# ADC3_2M.net
KiCad netlist of a schematic drawn in EAGLE
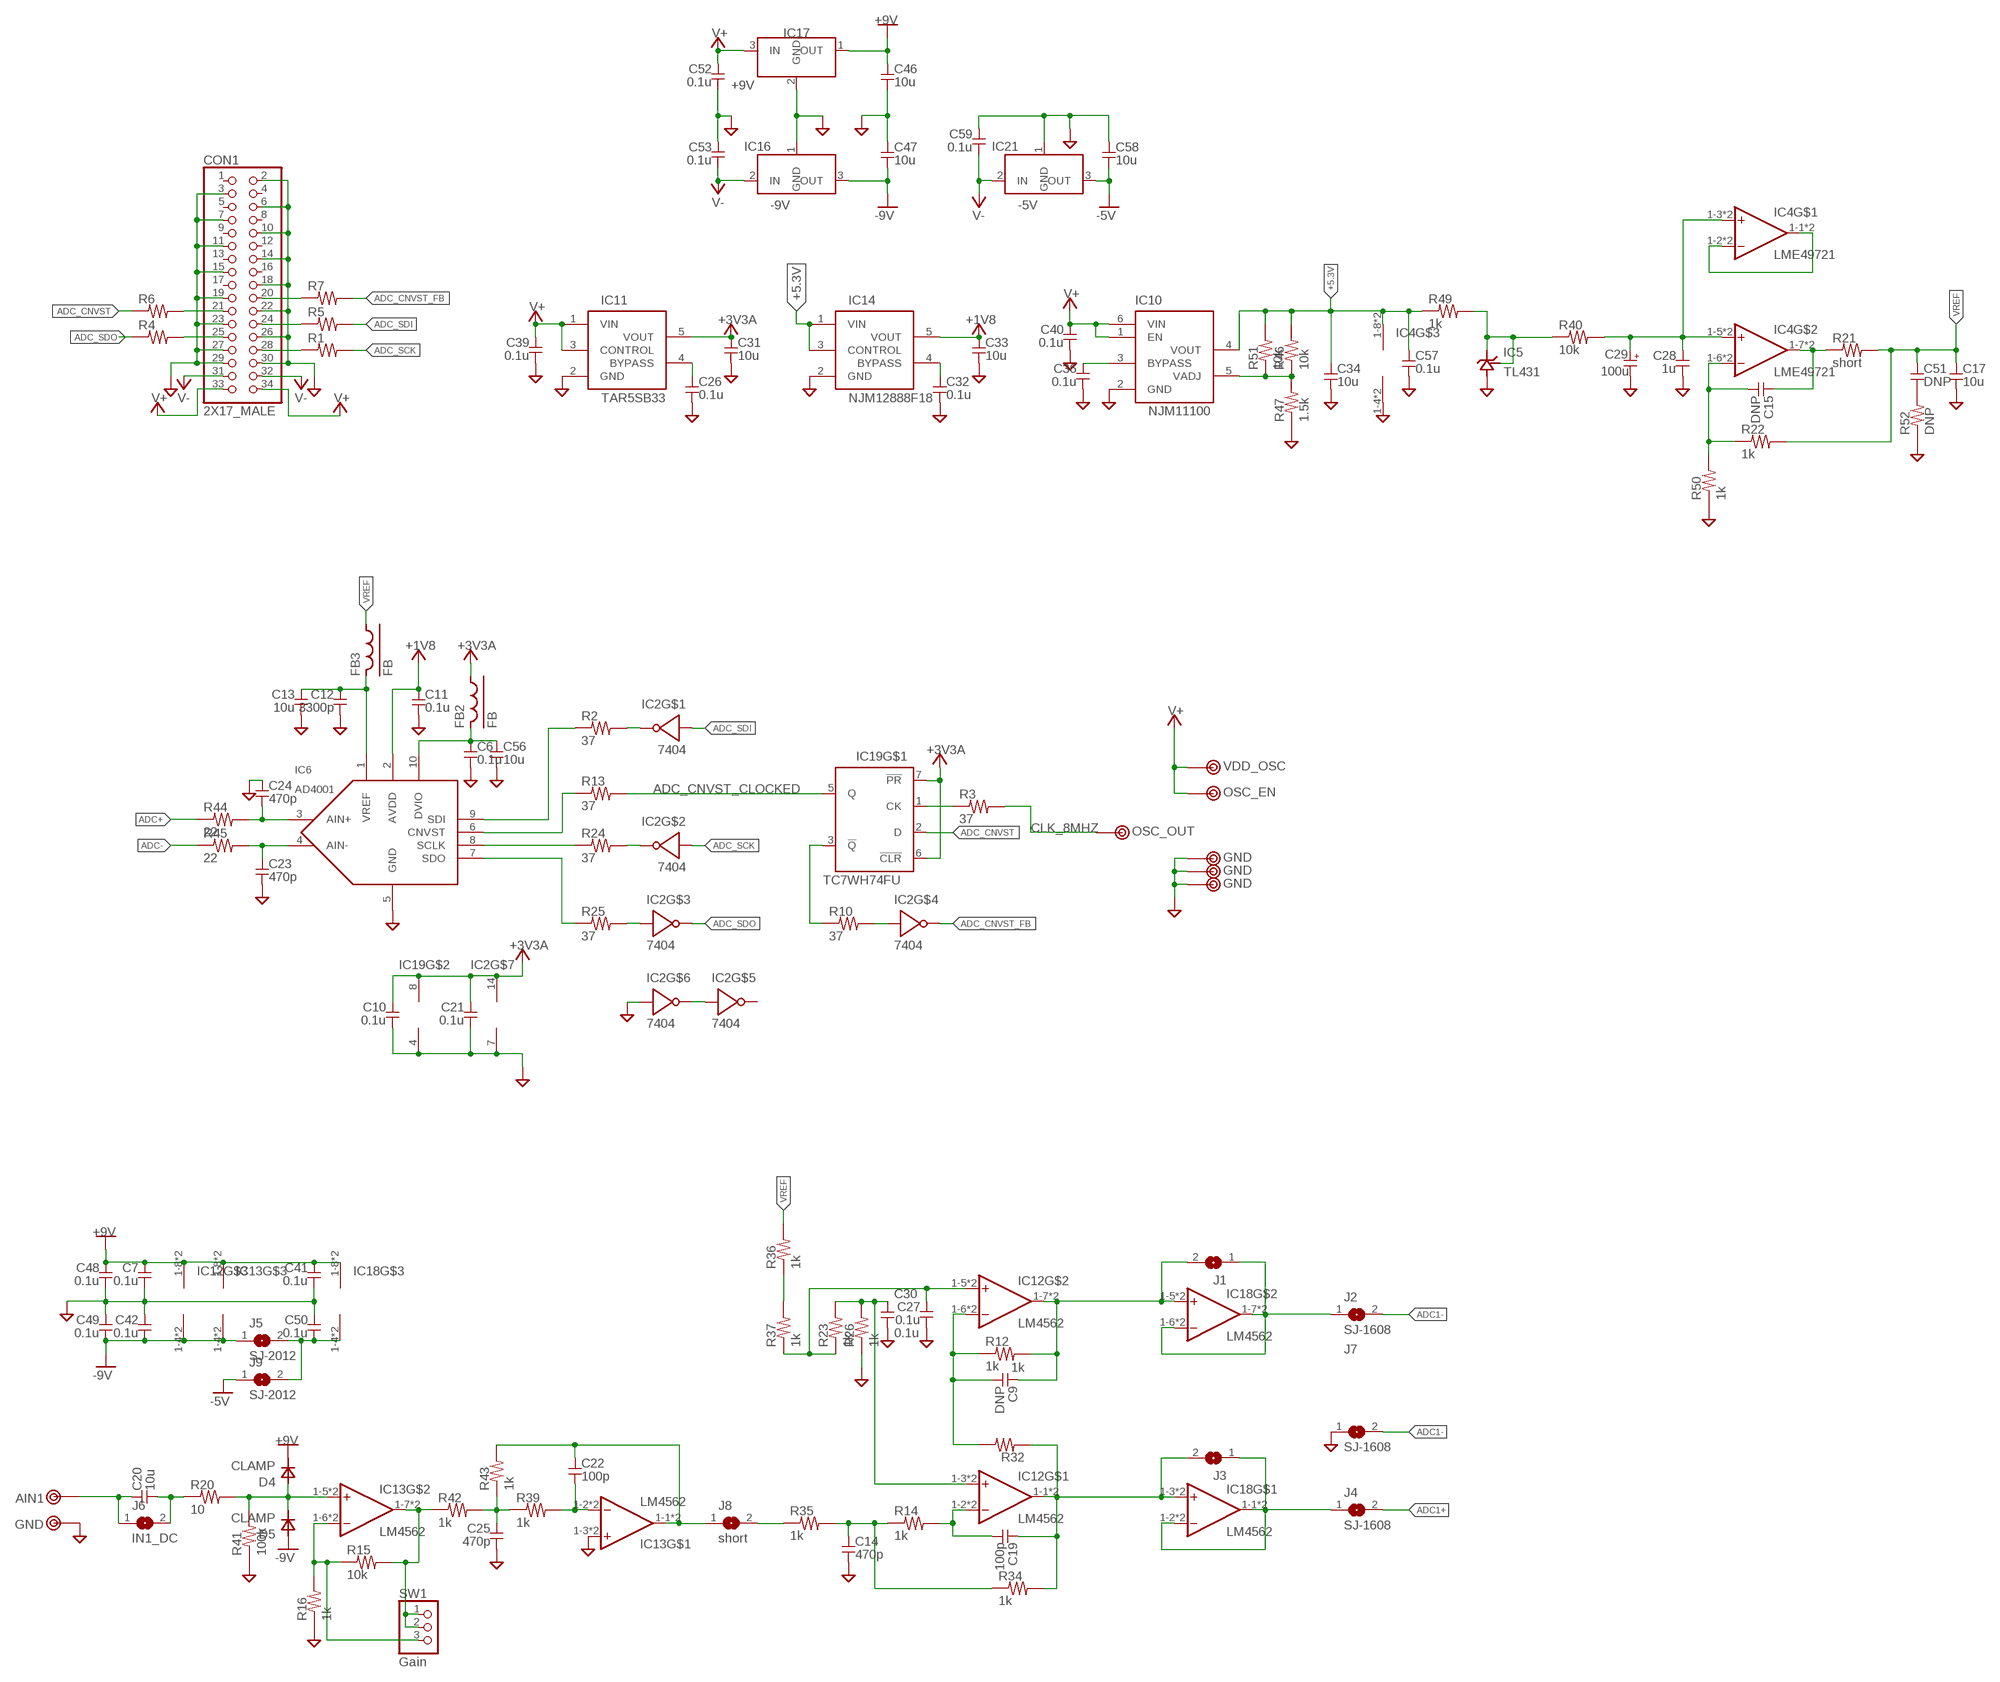
[diagram p0: schematic, sheet 1]

(export (version "E")
  (design (tool "Eeschema 10.0.6"))
  (components
    (comp (ref "C6")
      (value "0.1u")
      (footprint "eagle-import:1608")
      (libsource (lib "eagle-import") (part "C-1608"))
    )
    (comp (ref "C7")
      (value "0.1u")
      (footprint "eagle-import:1608")
      (libsource (lib "eagle-import") (part "C-1608"))
    )
    (comp (ref "C9")
      (value "DNP")
      (footprint "eagle-import:1608")
      (libsource (lib "eagle-import") (part "C-1608"))
    )
    (comp (ref "C10")
      (value "0.1u")
      (footprint "eagle-import:1608")
      (libsource (lib "eagle-import") (part "C-1608"))
    )
    (comp (ref "C11")
      (value "0.1u")
      (footprint "eagle-import:1608")
      (libsource (lib "eagle-import") (part "C-1608"))
    )
    (comp (ref "C12")
      (value "3300p")
      (footprint "eagle-import:1608")
      (libsource (lib "eagle-import") (part "C-1608"))
    )
    (comp (ref "C13")
      (value "10u")
      (footprint "eagle-import:2012")
      (libsource (lib "eagle-import") (part "C-2012"))
    )
    (comp (ref "C14")
      (value "470p")
      (footprint "eagle-import:1608")
      (libsource (lib "eagle-import") (part "C-1608"))
    )
    (comp (ref "C15")
      (value "DNP")
      (footprint "eagle-import:1608")
      (libsource (lib "eagle-import") (part "C-1608"))
    )
    (comp (ref "C17")
      (value "10u")
      (footprint "eagle-import:2012")
      (libsource (lib "eagle-import") (part "C-2012"))
    )
    (comp (ref "C19")
      (value "100p")
      (footprint "eagle-import:1608")
      (libsource (lib "eagle-import") (part "C-1608"))
    )
    (comp (ref "C20")
      (value "10u")
      (footprint "eagle-import:C050")
      (libsource (lib "eagle-import") (part "C-5"))
    )
    (comp (ref "C21")
      (value "0.1u")
      (footprint "eagle-import:1608")
      (libsource (lib "eagle-import") (part "C-1608"))
    )
    (comp (ref "C22")
      (value "100p")
      (footprint "eagle-import:1608")
      (libsource (lib "eagle-import") (part "C-1608"))
    )
    (comp (ref "C23")
      (value "470p")
      (footprint "eagle-import:1608")
      (libsource (lib "eagle-import") (part "C-1608"))
    )
    (comp (ref "C24")
      (value "470p")
      (footprint "eagle-import:1608")
      (libsource (lib "eagle-import") (part "C-1608"))
    )
    (comp (ref "C25")
      (value "470p")
      (footprint "eagle-import:1608")
      (libsource (lib "eagle-import") (part "C-1608"))
    )
    (comp (ref "C26")
      (value "0.1u")
      (footprint "eagle-import:1608")
      (libsource (lib "eagle-import") (part "C-1608"))
    )
    (comp (ref "C27")
      (value "0.1u")
      (footprint "eagle-import:1608")
      (libsource (lib "eagle-import") (part "C-1608"))
    )
    (comp (ref "C28")
      (value "1u")
      (footprint "eagle-import:1608")
      (libsource (lib "eagle-import") (part "C-1608"))
    )
    (comp (ref "C29")
      (value "100u")
      (footprint "eagle-import:E2.5-6.5")
      (libsource (lib "eagle-import") (part "CPOLE2.5-6.5"))
    )
    (comp (ref "C30")
      (value "0.1u")
      (footprint "eagle-import:1608")
      (libsource (lib "eagle-import") (part "C-1608"))
    )
    (comp (ref "C31")
      (value "10u")
      (footprint "eagle-import:2012")
      (libsource (lib "eagle-import") (part "C-2012"))
    )
    (comp (ref "C32")
      (value "0.1u")
      (footprint "eagle-import:1608")
      (libsource (lib "eagle-import") (part "C-1608"))
    )
    (comp (ref "C33")
      (value "10u")
      (footprint "eagle-import:2012")
      (libsource (lib "eagle-import") (part "C-2012"))
    )
    (comp (ref "C34")
      (value "10u")
      (footprint "eagle-import:2012")
      (libsource (lib "eagle-import") (part "C-2012"))
    )
    (comp (ref "C36")
      (value "0.1u")
      (footprint "eagle-import:1608")
      (libsource (lib "eagle-import") (part "C-1608"))
    )
    (comp (ref "C39")
      (value "0.1u")
      (footprint "eagle-import:1608")
      (libsource (lib "eagle-import") (part "C-1608"))
    )
    (comp (ref "C40")
      (value "0.1u")
      (footprint "eagle-import:1608")
      (libsource (lib "eagle-import") (part "C-1608"))
    )
    (comp (ref "C41")
      (value "0.1u")
      (footprint "eagle-import:1608")
      (libsource (lib "eagle-import") (part "C-1608"))
    )
    (comp (ref "C42")
      (value "0.1u")
      (footprint "eagle-import:1608")
      (libsource (lib "eagle-import") (part "C-1608"))
    )
    (comp (ref "C46")
      (value "10u")
      (footprint "eagle-import:3216")
      (libsource (lib "eagle-import") (part "C-3216"))
    )
    (comp (ref "C47")
      (value "10u")
      (footprint "eagle-import:3216")
      (libsource (lib "eagle-import") (part "C-3216"))
    )
    (comp (ref "C48")
      (value "0.1u")
      (footprint "eagle-import:1608")
      (libsource (lib "eagle-import") (part "C-1608"))
    )
    (comp (ref "C49")
      (value "0.1u")
      (footprint "eagle-import:1608")
      (libsource (lib "eagle-import") (part "C-1608"))
    )
    (comp (ref "C50")
      (value "0.1u")
      (footprint "eagle-import:1608")
      (libsource (lib "eagle-import") (part "C-1608"))
    )
    (comp (ref "C51")
      (value "DNP")
      (footprint "eagle-import:2012")
      (libsource (lib "eagle-import") (part "C-2012"))
    )
    (comp (ref "C52")
      (value "0.1u")
      (footprint "eagle-import:1608")
      (libsource (lib "eagle-import") (part "C-1608"))
    )
    (comp (ref "C53")
      (value "0.1u")
      (footprint "eagle-import:1608")
      (libsource (lib "eagle-import") (part "C-1608"))
    )
    (comp (ref "C56")
      (value "10u")
      (footprint "eagle-import:2012")
      (libsource (lib "eagle-import") (part "C-2012"))
    )
    (comp (ref "C57")
      (value "0.1u")
      (footprint "eagle-import:1608")
      (libsource (lib "eagle-import") (part "C-1608"))
    )
    (comp (ref "C58")
      (value "10u")
      (footprint "eagle-import:2012")
      (libsource (lib "eagle-import") (part "C-2012"))
    )
    (comp (ref "C59")
      (value "0.1u")
      (footprint "eagle-import:1608")
      (libsource (lib "eagle-import") (part "C-1608"))
    )
    (comp (ref "CON1")
      (value "2X17_MALE")
      (footprint "eagle-import:2X17_90")
      (libsource (lib "eagle-import") (part "2X17_MALE"))
    )
    (comp (ref "D4")
      (value "CLAMP")
      (footprint "eagle-import:SOD123")
      (libsource (lib "eagle-import") (part "DIODE-1N4148W"))
    )
    (comp (ref "D5")
      (value "CLAMP")
      (footprint "eagle-import:SOD123")
      (libsource (lib "eagle-import") (part "DIODE-1N4148W"))
    )
    (comp (ref "FB2")
      (value "FB")
      (footprint "eagle-import:1608-J")
      (libsource (lib "eagle-import") (part "FB"))
    )
    (comp (ref "FB3")
      (value "FB")
      (footprint "eagle-import:1608-J")
      (libsource (lib "eagle-import") (part "FB"))
    )
    (comp (ref "IC2")
      (value "7404")
      (footprint "eagle-import:TSSOP14")
      (libsource (lib "eagle-import") (part "7404"))
    )
    (comp (ref "IC4")
      (value "LME49721")
      (footprint "eagle-import:DIL8-SOP8")
      (libsource (lib "eagle-import") (part "OPA-2-DUAL"))
    )
    (comp (ref "IC5")
      (value "TL431")
      (footprint "eagle-import:TO-92")
      (libsource (lib "eagle-import") (part "TL431"))
    )
    (comp (ref "IC6")
      (value "AD4001")
      (footprint "eagle-import:MSOP10")
      (libsource (lib "eagle-import") (part "MCP331X1"))
    )
    (comp (ref "IC10")
      (value "NJM11100")
      (footprint "eagle-import:SOT23-6")
      (libsource (lib "eagle-import") (part "NJM11100"))
    )
    (comp (ref "IC11")
      (value "TAR5SB33")
      (footprint "eagle-import:SOT23-5")
      (libsource (lib "eagle-import") (part "TAR5SB33"))
    )
    (comp (ref "IC12")
      (value "LM4562")
      (footprint "eagle-import:DIL8-SOP8")
      (libsource (lib "eagle-import") (part "OPA-2-DUAL"))
    )
    (comp (ref "IC13")
      (value "LM4562")
      (footprint "eagle-import:DIL8-SOP8")
      (libsource (lib "eagle-import") (part "OPA-2-DUAL"))
    )
    (comp (ref "IC14")
      (value "NJM12888F18")
      (footprint "eagle-import:SOT23-5")
      (libsource (lib "eagle-import") (part "NJM12888"))
    )
    (comp (ref "IC16")
      (value "-9V")
      (footprint "eagle-import:TO-92")
      (libsource (lib "eagle-import") (part "79LX"))
    )
    (comp (ref "IC17")
      (value "+9V")
      (footprint "eagle-import:TO-92")
      (libsource (lib "eagle-import") (part "78LX"))
    )
    (comp (ref "IC18")
      (value "LM4562")
      (footprint "eagle-import:DIL8-SOP8")
      (libsource (lib "eagle-import") (part "OPA-2-DUAL"))
    )
    (comp (ref "IC19")
      (value "TC7WH74FU")
      (footprint "eagle-import:SSOP8-P-0.65")
      (libsource (lib "eagle-import") (part "TC7WH74FU"))
    )
    (comp (ref "IC21")
      (value "-5V")
      (footprint "eagle-import:TO-92")
      (libsource (lib "eagle-import") (part "79LX"))
    )
    (comp (ref "J1")
      (value "SJ-2012")
      (footprint "eagle-import:2012-J")
      (libsource (lib "eagle-import") (part "SJ-2012"))
    )
    (comp (ref "J2")
      (value "SJ-1608")
      (footprint "eagle-import:1608-J")
      (libsource (lib "eagle-import") (part "SJ-1608"))
    )
    (comp (ref "J3")
      (value "SJ-2012")
      (footprint "eagle-import:2012-J")
      (libsource (lib "eagle-import") (part "SJ-2012"))
    )
    (comp (ref "J4")
      (value "SJ-1608")
      (footprint "eagle-import:1608-J")
      (libsource (lib "eagle-import") (part "SJ-1608"))
    )
    (comp (ref "J5")
      (value "SJ-2012")
      (footprint "eagle-import:2012-J")
      (libsource (lib "eagle-import") (part "SJ-2012"))
    )
    (comp (ref "J6")
      (value "IN1_DC")
      (footprint "eagle-import:2012-J")
      (libsource (lib "eagle-import") (part "SJ-2012"))
    )
    (comp (ref "J7")
      (value "SJ-1608")
      (footprint "eagle-import:1608-J")
      (libsource (lib "eagle-import") (part "SJ-1608"))
    )
    (comp (ref "J8")
      (value "short")
      (footprint "eagle-import:2012-J")
      (libsource (lib "eagle-import") (part "SJ-2012"))
    )
    (comp (ref "J9")
      (value "SJ-2012")
      (footprint "eagle-import:2012-J")
      (libsource (lib "eagle-import") (part "SJ-2012"))
    )
    (comp (ref "R1")
      (value "R-1608J")
      (footprint "eagle-import:1608-J")
      (libsource (lib "eagle-import") (part "R-1608J"))
    )
    (comp (ref "R2")
      (value "37")
      (footprint "eagle-import:1608-J")
      (libsource (lib "eagle-import") (part "R-1608J"))
    )
    (comp (ref "R3")
      (value "37")
      (footprint "eagle-import:1608-J")
      (libsource (lib "eagle-import") (part "R-1608J"))
    )
    (comp (ref "R4")
      (value "R-1608J")
      (footprint "eagle-import:1608-J")
      (libsource (lib "eagle-import") (part "R-1608J"))
    )
    (comp (ref "R5")
      (value "R-1608J")
      (footprint "eagle-import:1608-J")
      (libsource (lib "eagle-import") (part "R-1608J"))
    )
    (comp (ref "R6")
      (value "R-1608J")
      (footprint "eagle-import:1608-J")
      (libsource (lib "eagle-import") (part "R-1608J"))
    )
    (comp (ref "R7")
      (value "R-1608J")
      (footprint "eagle-import:1608-J")
      (libsource (lib "eagle-import") (part "R-1608J"))
    )
    (comp (ref "R10")
      (value "37")
      (footprint "eagle-import:1608-J")
      (libsource (lib "eagle-import") (part "R-1608J"))
    )
    (comp (ref "R12")
      (value "1k")
      (footprint "eagle-import:1608")
      (libsource (lib "eagle-import") (part "R-1608"))
    )
    (comp (ref "R13")
      (value "37")
      (footprint "eagle-import:1608-J")
      (libsource (lib "eagle-import") (part "R-1608J"))
    )
    (comp (ref "R14")
      (value "1k")
      (footprint "eagle-import:1608")
      (libsource (lib "eagle-import") (part "R-1608"))
    )
    (comp (ref "R15")
      (value "10k")
      (footprint "eagle-import:1608")
      (libsource (lib "eagle-import") (part "R-1608"))
    )
    (comp (ref "R16")
      (value "1k")
      (footprint "eagle-import:1608")
      (libsource (lib "eagle-import") (part "R-1608"))
    )
    (comp (ref "R20")
      (value "10")
      (footprint "eagle-import:1608-J")
      (libsource (lib "eagle-import") (part "R-1608J"))
    )
    (comp (ref "R21")
      (value "short")
      (footprint "eagle-import:1608-J")
      (libsource (lib "eagle-import") (part "R-1608J"))
    )
    (comp (ref "R22")
      (value "1k")
      (footprint "eagle-import:1608")
      (libsource (lib "eagle-import") (part "R-1608"))
    )
    (comp (ref "R23")
      (value "1k")
      (footprint "eagle-import:1608")
      (libsource (lib "eagle-import") (part "R-1608"))
    )
    (comp (ref "R24")
      (value "37")
      (footprint "eagle-import:1608-J")
      (libsource (lib "eagle-import") (part "R-1608J"))
    )
    (comp (ref "R25")
      (value "37")
      (footprint "eagle-import:1608-J")
      (libsource (lib "eagle-import") (part "R-1608J"))
    )
    (comp (ref "R26")
      (value "1k")
      (footprint "eagle-import:1608")
      (libsource (lib "eagle-import") (part "R-1608"))
    )
    (comp (ref "R32")
      (value "1k")
      (footprint "eagle-import:1608")
      (libsource (lib "eagle-import") (part "R-1608"))
    )
    (comp (ref "R34")
      (value "1k")
      (footprint "eagle-import:1608")
      (libsource (lib "eagle-import") (part "R-1608"))
    )
    (comp (ref "R35")
      (value "1k")
      (footprint "eagle-import:1608")
      (libsource (lib "eagle-import") (part "R-1608"))
    )
    (comp (ref "R36")
      (value "1k")
      (footprint "eagle-import:1608")
      (libsource (lib "eagle-import") (part "R-1608"))
    )
    (comp (ref "R37")
      (value "1k")
      (footprint "eagle-import:1608")
      (libsource (lib "eagle-import") (part "R-1608"))
    )
    (comp (ref "R39")
      (value "1k")
      (footprint "eagle-import:1608")
      (libsource (lib "eagle-import") (part "R-1608"))
    )
    (comp (ref "R40")
      (value "10k")
      (footprint "eagle-import:1608")
      (libsource (lib "eagle-import") (part "R-1608"))
    )
    (comp (ref "R41")
      (value "100k")
      (footprint "eagle-import:1608")
      (libsource (lib "eagle-import") (part "R-1608"))
    )
    (comp (ref "R42")
      (value "1k")
      (footprint "eagle-import:1608")
      (libsource (lib "eagle-import") (part "R-1608"))
    )
    (comp (ref "R43")
      (value "1k")
      (footprint "eagle-import:1608")
      (libsource (lib "eagle-import") (part "R-1608"))
    )
    (comp (ref "R44")
      (value "22")
      (footprint "eagle-import:1608")
      (libsource (lib "eagle-import") (part "R-1608"))
    )
    (comp (ref "R45")
      (value "22")
      (footprint "eagle-import:1608")
      (libsource (lib "eagle-import") (part "R-1608"))
    )
    (comp (ref "R46")
      (value "10k")
      (footprint "eagle-import:1608")
      (libsource (lib "eagle-import") (part "R-1608"))
    )
    (comp (ref "R47")
      (value "1.5k")
      (footprint "eagle-import:1608")
      (libsource (lib "eagle-import") (part "R-1608"))
    )
    (comp (ref "R49")
      (value "1k")
      (footprint "eagle-import:1608")
      (libsource (lib "eagle-import") (part "R-1608"))
    )
    (comp (ref "R50")
      (value "1k")
      (footprint "eagle-import:1608")
      (libsource (lib "eagle-import") (part "R-1608"))
    )
    (comp (ref "R51")
      (value "10k")
      (footprint "eagle-import:1608")
      (libsource (lib "eagle-import") (part "R-1608"))
    )
    (comp (ref "R52")
      (value "DNP")
      (footprint "eagle-import:2012")
      (libsource (lib "eagle-import") (part "R-2012"))
    )
    (comp (ref "SW1")
      (value "Gain")
      (footprint "eagle-import:1X03")
      (libsource (lib "eagle-import") (part "SW-1X3"))
    )
    (comp (ref "TP2")
      (value "AIN1")
      (footprint "eagle-import:TESTPIN-BIG")
      (libsource (lib "eagle-import") (part "TESTPIN-BIG"))
    )
    (comp (ref "TP16")
      (value "GND")
      (footprint "eagle-import:TESTPIN-BIG")
      (libsource (lib "eagle-import") (part "TESTPIN-BIG"))
    )
    (comp (ref "TP24")
      (value "VDD_OSC")
      (footprint "eagle-import:TESTPIN")
      (libsource (lib "eagle-import") (part "TESTPIN"))
    )
    (comp (ref "TP25")
      (value "OSC_EN")
      (footprint "eagle-import:TESTPIN")
      (libsource (lib "eagle-import") (part "TESTPIN"))
    )
    (comp (ref "TP26")
      (value "OSC_OUT")
      (footprint "eagle-import:TESTPIN")
      (libsource (lib "eagle-import") (part "TESTPIN"))
    )
    (comp (ref "TP27")
      (value "GND")
      (footprint "eagle-import:TESTPIN")
      (libsource (lib "eagle-import") (part "TESTPIN"))
    )
    (comp (ref "TP28")
      (value "GND")
      (footprint "eagle-import:TESTPIN")
      (libsource (lib "eagle-import") (part "TESTPIN"))
    )
    (comp (ref "TP29")
      (value "GND")
      (footprint "eagle-import:TESTPIN")
      (libsource (lib "eagle-import") (part "TESTPIN"))
    )
  )
  (nets
    (net (code "1") (name "+1V8") (class "Default")
      (node (ref "C11") (pin "1") (pinfunction "1_1") (pintype "passive"))
      (node (ref "C33") (pin "1") (pinfunction "1_1") (pintype "passive"))
      (node (ref "IC14") (pin "5") (pinfunction "VOUT_5") (pintype "power_in"))
      (node (ref "IC6") (pin "2") (pinfunction "AVDD_2") (pintype "power_in"))
    )
    (net (code "2") (name "+3V3A") (class "Default")
      (node (ref "C10") (pin "1") (pinfunction "1_1") (pintype "passive"))
      (node (ref "C21") (pin "1") (pinfunction "1_1") (pintype "passive"))
      (node (ref "C31") (pin "1") (pinfunction "1_1") (pintype "passive"))
      (node (ref "FB2") (pin "1") (pinfunction "1_1") (pintype "passive"))
      (node (ref "IC11") (pin "5") (pinfunction "VOUT_5") (pintype "power_in"))
      (node (ref "IC19") (pin "6") (pinfunction "~{CLR}_6") (pintype "input"))
      (node (ref "IC19") (pin "7") (pinfunction "~{PR}_7") (pintype "input"))
      (node (ref "IC19") (pin "8") (pinfunction "V+_8") (pintype "power_in"))
      (node (ref "IC2") (pin "14") (pinfunction "V+_14") (pintype "power_in"))
    )
    (net (code "3") (name "+5.3V") (class "Default")
      (node (ref "C34") (pin "1") (pinfunction "1_1") (pintype "passive"))
      (node (ref "C57") (pin "1") (pinfunction "1_1") (pintype "passive"))
      (node (ref "IC10") (pin "4") (pinfunction "VOUT_4") (pintype "output"))
      (node (ref "IC14") (pin "1") (pinfunction "VIN_1") (pintype "power_in"))
      (node (ref "IC14") (pin "3") (pinfunction "CONTROL_3") (pintype "input"))
      (node (ref "IC4") (pin "1-8") (pinfunction "V+_1-8") (pintype "power_in"))
      (node (ref "IC4") (pin "2-8") (pinfunction "V+_2-8") (pintype "power_in"))
      (node (ref "R46") (pin "2") (pinfunction "2_2") (pintype "passive"))
      (node (ref "R49") (pin "1") (pinfunction "1_1") (pintype "passive"))
      (node (ref "R51") (pin "2") (pinfunction "2_2") (pintype "passive"))
    )
    (net (code "4") (name "+9V") (class "Default")
      (node (ref "C41") (pin "1") (pinfunction "1_1") (pintype "passive"))
      (node (ref "C46") (pin "1") (pinfunction "1_1") (pintype "passive"))
      (node (ref "C48") (pin "1") (pinfunction "1_1") (pintype "passive"))
      (node (ref "C7") (pin "1") (pinfunction "1_1") (pintype "passive"))
      (node (ref "D4") (pin "2") (pinfunction "K_2") (pintype "passive"))
      (node (ref "IC12") (pin "1-8") (pinfunction "V+_1-8") (pintype "power_in"))
      (node (ref "IC12") (pin "2-8") (pinfunction "V+_2-8") (pintype "power_in"))
      (node (ref "IC13") (pin "1-8") (pinfunction "V+_1-8") (pintype "power_in"))
      (node (ref "IC13") (pin "2-8") (pinfunction "V+_2-8") (pintype "power_in"))
      (node (ref "IC17") (pin "1") (pinfunction "OUT_1") (pintype "output"))
      (node (ref "IC18") (pin "1-8") (pinfunction "V+_1-8") (pintype "power_in"))
      (node (ref "IC18") (pin "2-8") (pinfunction "V+_2-8") (pintype "power_in"))
    )
    (net (code "5") (name "-5V") (class "Default")
      (node (ref "C58") (pin "2") (pinfunction "2_2") (pintype "passive"))
      (node (ref "IC21") (pin "3") (pinfunction "OUT_3") (pintype "output"))
      (node (ref "J9") (pin "1") (pinfunction "1_1") (pintype "passive"))
    )
    (net (code "6") (name "-9V") (class "Default")
      (node (ref "C42") (pin "2") (pinfunction "2_2") (pintype "passive"))
      (node (ref "C47") (pin "2") (pinfunction "2_2") (pintype "passive"))
      (node (ref "C49") (pin "2") (pinfunction "2_2") (pintype "passive"))
      (node (ref "D5") (pin "1") (pinfunction "A_1") (pintype "passive"))
      (node (ref "IC12") (pin "1-4") (pinfunction "V-_1-4") (pintype "power_in"))
      (node (ref "IC12") (pin "2-4") (pinfunction "V-_2-4") (pintype "power_in"))
      (node (ref "IC13") (pin "1-4") (pinfunction "V-_1-4") (pintype "power_in"))
      (node (ref "IC13") (pin "2-4") (pinfunction "V-_2-4") (pintype "power_in"))
      (node (ref "IC16") (pin "3") (pinfunction "OUT_3") (pintype "output"))
      (node (ref "J5") (pin "1") (pinfunction "1_1") (pintype "passive"))
    )
    (net (code "7") (name "/ADC_CNVST_CLOCKED") (class "Default")
      (node (ref "IC19") (pin "5") (pinfunction "Q_5") (pintype "output"))
      (node (ref "R13") (pin "2") (pinfunction "2_2") (pintype "passive"))
    )
    (net (code "8") (name "/CLK_8MHZ") (class "Default")
      (node (ref "R3") (pin "2") (pinfunction "2_2") (pintype "passive"))
      (node (ref "TP26") (pin "1") (pinfunction "1_1") (pintype "passive"))
    )
    (net (code "9") (name "ADC+") (class "Default")
      (node (ref "R44") (pin "1") (pinfunction "1_1") (pintype "passive"))
    )
    (net (code "10") (name "ADC-") (class "Default")
      (node (ref "R45") (pin "1") (pinfunction "1_1") (pintype "passive"))
    )
    (net (code "11") (name "ADC1+") (class "Default")
      (node (ref "J4") (pin "2") (pinfunction "2_2") (pintype "passive"))
    )
    (net (code "12") (name "ADC1-") (class "Default")
      (node (ref "J2") (pin "2") (pinfunction "2_2") (pintype "passive"))
      (node (ref "J7") (pin "2") (pinfunction "2_2") (pintype "passive"))
    )
    (net (code "13") (name "ADC_CNVST") (class "Default")
      (node (ref "IC19") (pin "2") (pinfunction "D_2") (pintype "input"))
      (node (ref "R6") (pin "1") (pinfunction "1_1") (pintype "passive"))
    )
    (net (code "14") (name "ADC_CNVST_FB") (class "Default")
      (node (ref "IC2") (pin "8") (pinfunction "OUT_8") (pintype "output"))
      (node (ref "R7") (pin "2") (pinfunction "2_2") (pintype "passive"))
    )
    (net (code "15") (name "ADC_SCK") (class "Default")
      (node (ref "IC2") (pin "3") (pinfunction "IN_3") (pintype "input"))
      (node (ref "R1") (pin "2") (pinfunction "2_2") (pintype "passive"))
    )
    (net (code "16") (name "ADC_SDI") (class "Default")
      (node (ref "IC2") (pin "1") (pinfunction "IN_1") (pintype "input"))
      (node (ref "R5") (pin "2") (pinfunction "2_2") (pintype "passive"))
    )
    (net (code "17") (name "ADC_SDO") (class "Default")
      (node (ref "IC2") (pin "6") (pinfunction "OUT_6") (pintype "output"))
      (node (ref "R4") (pin "1") (pinfunction "1_1") (pintype "passive"))
    )
    (net (code "18") (name "GND") (class "Default")
      (node (ref "C10") (pin "2") (pinfunction "2_2") (pintype "passive"))
      (node (ref "C11") (pin "2") (pinfunction "2_2") (pintype "passive"))
      (node (ref "C12") (pin "2") (pinfunction "2_2") (pintype "passive"))
      (node (ref "C13") (pin "2") (pinfunction "2_2") (pintype "passive"))
      (node (ref "C14") (pin "2") (pinfunction "2_2") (pintype "passive"))
      (node (ref "C17") (pin "2") (pinfunction "2_2") (pintype "passive"))
      (node (ref "C21") (pin "2") (pinfunction "2_2") (pintype "passive"))
      (node (ref "C23") (pin "2") (pinfunction "2_2") (pintype "passive"))
      (node (ref "C24") (pin "1") (pinfunction "1_1") (pintype "passive"))
      (node (ref "C25") (pin "2") (pinfunction "2_2") (pintype "passive"))
      (node (ref "C26") (pin "2") (pinfunction "2_2") (pintype "passive"))
      (node (ref "C27") (pin "2") (pinfunction "2_2") (pintype "passive"))
      (node (ref "C28") (pin "2") (pinfunction "2_2") (pintype "passive"))
      (node (ref "C29") (pin "-") (pinfunction "2_-") (pintype "passive"))
      (node (ref "C30") (pin "2") (pinfunction "2_2") (pintype "passive"))
      (node (ref "C31") (pin "2") (pinfunction "2_2") (pintype "passive"))
      (node (ref "C32") (pin "2") (pinfunction "2_2") (pintype "passive"))
      (node (ref "C33") (pin "2") (pinfunction "2_2") (pintype "passive"))
      (node (ref "C34") (pin "2") (pinfunction "2_2") (pintype "passive"))
      (node (ref "C36") (pin "2") (pinfunction "2_2") (pintype "passive"))
      (node (ref "C39") (pin "2") (pinfunction "2_2") (pintype "passive"))
      (node (ref "C40") (pin "2") (pinfunction "2_2") (pintype "passive"))
      (node (ref "C41") (pin "2") (pinfunction "2_2") (pintype "passive"))
      (node (ref "C42") (pin "1") (pinfunction "1_1") (pintype "passive"))
      (node (ref "C46") (pin "2") (pinfunction "2_2") (pintype "passive"))
      (node (ref "C47") (pin "1") (pinfunction "1_1") (pintype "passive"))
      (node (ref "C48") (pin "2") (pinfunction "2_2") (pintype "passive"))
      (node (ref "C49") (pin "1") (pinfunction "1_1") (pintype "passive"))
      (node (ref "C50") (pin "1") (pinfunction "1_1") (pintype "passive"))
      (node (ref "C52") (pin "2") (pinfunction "2_2") (pintype "passive"))
      (node (ref "C53") (pin "1") (pinfunction "1_1") (pintype "passive"))
      (node (ref "C56") (pin "2") (pinfunction "2_2") (pintype "passive"))
      (node (ref "C57") (pin "2") (pinfunction "2_2") (pintype "passive"))
      (node (ref "C58") (pin "1") (pinfunction "1_1") (pintype "passive"))
      (node (ref "C59") (pin "1") (pinfunction "1_1") (pintype "passive"))
      (node (ref "C6") (pin "2") (pinfunction "2_2") (pintype "passive"))
      (node (ref "C7") (pin "2") (pinfunction "2_2") (pintype "passive"))
      (node (ref "CON1") (pin "10") (pinfunction "10_10") (pintype "passive"))
      (node (ref "CON1") (pin "11") (pinfunction "11_11") (pintype "passive"))
      (node (ref "CON1") (pin "14") (pinfunction "14_14") (pintype "passive"))
      (node (ref "CON1") (pin "15") (pinfunction "15_15") (pintype "passive"))
      (node (ref "CON1") (pin "18") (pinfunction "18_18") (pintype "passive"))
      (node (ref "CON1") (pin "19") (pinfunction "19_19") (pintype "passive"))
      (node (ref "CON1") (pin "2") (pinfunction "2_2") (pintype "passive"))
      (node (ref "CON1") (pin "22") (pinfunction "22_22") (pintype "passive"))
      (node (ref "CON1") (pin "23") (pinfunction "23_23") (pintype "passive"))
      (node (ref "CON1") (pin "26") (pinfunction "26_26") (pintype "passive"))
      (node (ref "CON1") (pin "27") (pinfunction "27_27") (pintype "passive"))
      (node (ref "CON1") (pin "29") (pinfunction "29_29") (pintype "passive"))
      (node (ref "CON1") (pin "3") (pinfunction "3_3") (pintype "passive"))
      (node (ref "CON1") (pin "30") (pinfunction "30_30") (pintype "passive"))
      (node (ref "CON1") (pin "6") (pinfunction "6_6") (pintype "passive"))
      (node (ref "CON1") (pin "7") (pinfunction "7_7") (pintype "passive"))
      (node (ref "IC10") (pin "2") (pinfunction "GND_2") (pintype "power_in"))
      (node (ref "IC11") (pin "2") (pinfunction "GND_2") (pintype "power_in"))
      (node (ref "IC13") (pin "1-3") (pinfunction "+IN_1-3") (pintype "input"))
      (node (ref "IC13") (pin "2-3") (pinfunction "+IN_2-3") (pintype "input"))
      (node (ref "IC14") (pin "2") (pinfunction "GND_2") (pintype "power_in"))
      (node (ref "IC16") (pin "1") (pinfunction "GND_1") (pintype "input"))
      (node (ref "IC17") (pin "2") (pinfunction "GND_2") (pintype "power_in"))
      (node (ref "IC19") (pin "4") (pinfunction "V-_4") (pintype "power_in"))
      (node (ref "IC2") (pin "13") (pinfunction "IN_13") (pintype "input"))
      (node (ref "IC2") (pin "7") (pinfunction "V-_7") (pintype "power_in"))
      (node (ref "IC21") (pin "1") (pinfunction "GND_1") (pintype "input"))
      (node (ref "IC4") (pin "1-4") (pinfunction "V-_1-4") (pintype "power_in"))
      (node (ref "IC4") (pin "2-4") (pinfunction "V-_2-4") (pintype "power_in"))
      (node (ref "IC5") (pin "2") (pinfunction "GND_2") (pintype "bidirectional"))
      (node (ref "IC6") (pin "5") (pinfunction "GND_5") (pintype "power_in"))
      (node (ref "J7") (pin "1") (pinfunction "1_1") (pintype "passive"))
      (node (ref "R16") (pin "1") (pinfunction "1_1") (pintype "passive"))
      (node (ref "R26") (pin "1") (pinfunction "1_1") (pintype "passive"))
      (node (ref "R41") (pin "1") (pinfunction "1_1") (pintype "passive"))
      (node (ref "R47") (pin "1") (pinfunction "1_1") (pintype "passive"))
      (node (ref "R50") (pin "1") (pinfunction "1_1") (pintype "passive"))
      (node (ref "R52") (pin "1") (pinfunction "1_1") (pintype "passive"))
      (node (ref "TP16") (pin "1") (pinfunction "1_1") (pintype "passive"))
      (node (ref "TP27") (pin "1") (pinfunction "1_1") (pintype "passive"))
      (node (ref "TP28") (pin "1") (pinfunction "1_1") (pintype "passive"))
      (node (ref "TP29") (pin "1") (pinfunction "1_1") (pintype "passive"))
    )
    (net (code "19") (name "Net-(C9-Pad1)") (class "Default")
      (node (ref "C9") (pin "1") (pinfunction "1_1") (pintype "passive"))
      (node (ref "IC12") (pin "1-7") (pinfunction "OUT_1-7") (pintype "output"))
      (node (ref "IC12") (pin "2-7") (pinfunction "OUT_2-7") (pintype "output"))
      (node (ref "IC18") (pin "1-5") (pinfunction "+IN_1-5") (pintype "input"))
      (node (ref "IC18") (pin "2-5") (pinfunction "+IN_2-5") (pintype "input"))
      (node (ref "J1") (pin "2") (pinfunction "2_2") (pintype "passive"))
      (node (ref "R12") (pin "2") (pinfunction "2_2") (pintype "passive"))
    )
    (net (code "20") (name "Net-(C9-Pad2)") (class "Default")
      (node (ref "C9") (pin "2") (pinfunction "2_2") (pintype "passive"))
      (node (ref "IC12") (pin "1-6") (pinfunction "-IN_1-6") (pintype "input"))
      (node (ref "IC12") (pin "2-6") (pinfunction "-IN_2-6") (pintype "input"))
      (node (ref "R12") (pin "1") (pinfunction "1_1") (pintype "passive"))
      (node (ref "R32") (pin "2") (pinfunction "2_2") (pintype "passive"))
    )
    (net (code "21") (name "Net-(C14-Pad1)") (class "Default")
      (node (ref "C14") (pin "1") (pinfunction "1_1") (pintype "passive"))
      (node (ref "R14") (pin "1") (pinfunction "1_1") (pintype "passive"))
      (node (ref "R34") (pin "1") (pinfunction "1_1") (pintype "passive"))
      (node (ref "R35") (pin "2") (pinfunction "2_2") (pintype "passive"))
    )
    (net (code "22") (name "Net-(C15-Pad1)") (class "Default")
      (node (ref "C15") (pin "1") (pinfunction "1_1") (pintype "passive"))
      (node (ref "IC4") (pin "1-7") (pinfunction "OUT_1-7") (pintype "output"))
      (node (ref "IC4") (pin "2-7") (pinfunction "OUT_2-7") (pintype "output"))
      (node (ref "R21") (pin "1") (pinfunction "1_1") (pintype "passive"))
    )
    (net (code "23") (name "Net-(C15-Pad2)") (class "Default")
      (node (ref "C15") (pin "2") (pinfunction "2_2") (pintype "passive"))
      (node (ref "IC4") (pin "1-6") (pinfunction "-IN_1-6") (pintype "input"))
      (node (ref "IC4") (pin "2-6") (pinfunction "-IN_2-6") (pintype "input"))
      (node (ref "R22") (pin "1") (pinfunction "1_1") (pintype "passive"))
      (node (ref "R50") (pin "2") (pinfunction "2_2") (pintype "passive"))
    )
    (net (code "24") (name "Net-(C19-Pad1)") (class "Default")
      (node (ref "C19") (pin "1") (pinfunction "1_1") (pintype "passive"))
      (node (ref "IC12") (pin "1-1") (pinfunction "OUT_1-1") (pintype "output"))
      (node (ref "IC12") (pin "2-1") (pinfunction "OUT_2-1") (pintype "output"))
      (node (ref "IC18") (pin "1-3") (pinfunction "+IN_1-3") (pintype "input"))
      (node (ref "IC18") (pin "2-3") (pinfunction "+IN_2-3") (pintype "input"))
      (node (ref "J3") (pin "2") (pinfunction "2_2") (pintype "passive"))
      (node (ref "R32") (pin "1") (pinfunction "1_1") (pintype "passive"))
      (node (ref "R34") (pin "2") (pinfunction "2_2") (pintype "passive"))
    )
    (net (code "25") (name "Net-(C19-Pad2)") (class "Default")
      (node (ref "C19") (pin "2") (pinfunction "2_2") (pintype "passive"))
      (node (ref "IC12") (pin "1-2") (pinfunction "-IN_1-2") (pintype "input"))
      (node (ref "IC12") (pin "2-2") (pinfunction "-IN_2-2") (pintype "input"))
      (node (ref "R14") (pin "2") (pinfunction "2_2") (pintype "passive"))
    )
    (net (code "26") (name "Net-(C20-Pad1)") (class "Default")
      (node (ref "C20") (pin "1") (pinfunction "1_1") (pintype "passive"))
      (node (ref "J6") (pin "1") (pinfunction "1_1") (pintype "passive"))
      (node (ref "TP2") (pin "1") (pinfunction "1_1") (pintype "passive"))
    )
    (net (code "27") (name "Net-(C20-Pad2)") (class "Default")
      (node (ref "C20") (pin "2") (pinfunction "2_2") (pintype "passive"))
      (node (ref "J6") (pin "2") (pinfunction "2_2") (pintype "passive"))
      (node (ref "R20") (pin "1") (pinfunction "1_1") (pintype "passive"))
    )
    (net (code "28") (name "Net-(C22-Pad1)") (class "Default")
      (node (ref "C22") (pin "1") (pinfunction "1_1") (pintype "passive"))
      (node (ref "IC13") (pin "1-1") (pinfunction "OUT_1-1") (pintype "output"))
      (node (ref "IC13") (pin "2-1") (pinfunction "OUT_2-1") (pintype "output"))
      (node (ref "J8") (pin "1") (pinfunction "1_1") (pintype "passive"))
      (node (ref "R43") (pin "2") (pinfunction "2_2") (pintype "passive"))
    )
    (net (code "29") (name "Net-(C22-Pad2)") (class "Default")
      (node (ref "C22") (pin "2") (pinfunction "2_2") (pintype "passive"))
      (node (ref "IC13") (pin "1-2") (pinfunction "-IN_1-2") (pintype "input"))
      (node (ref "IC13") (pin "2-2") (pinfunction "-IN_2-2") (pintype "input"))
      (node (ref "R39") (pin "2") (pinfunction "2_2") (pintype "passive"))
    )
    (net (code "30") (name "Net-(C25-Pad1)") (class "Default")
      (node (ref "C25") (pin "1") (pinfunction "1_1") (pintype "passive"))
      (node (ref "R39") (pin "1") (pinfunction "1_1") (pintype "passive"))
      (node (ref "R42") (pin "2") (pinfunction "2_2") (pintype "passive"))
      (node (ref "R43") (pin "1") (pinfunction "1_1") (pintype "passive"))
    )
    (net (code "31") (name "Net-(C27-Pad1)") (class "Default")
      (node (ref "C27") (pin "1") (pinfunction "1_1") (pintype "passive"))
      (node (ref "IC12") (pin "1-5") (pinfunction "+IN_1-5") (pintype "input"))
      (node (ref "IC12") (pin "2-5") (pinfunction "+IN_2-5") (pintype "input"))
      (node (ref "R23") (pin "1") (pinfunction "1_1") (pintype "passive"))
      (node (ref "R37") (pin "1") (pinfunction "1_1") (pintype "passive"))
    )
    (net (code "32") (name "Net-(C29-1)") (class "Default")
      (node (ref "C28") (pin "1") (pinfunction "1_1") (pintype "passive"))
      (node (ref "C29") (pin "+") (pinfunction "1_+") (pintype "passive"))
      (node (ref "IC4") (pin "1-3") (pinfunction "+IN_1-3") (pintype "input"))
      (node (ref "IC4") (pin "1-5") (pinfunction "+IN_1-5") (pintype "input"))
      (node (ref "IC4") (pin "2-3") (pinfunction "+IN_2-3") (pintype "input"))
      (node (ref "IC4") (pin "2-5") (pinfunction "+IN_2-5") (pintype "input"))
      (node (ref "R40") (pin "2") (pinfunction "2_2") (pintype "passive"))
    )
    (net (code "33") (name "Net-(C30-Pad1)") (class "Default")
      (node (ref "C30") (pin "1") (pinfunction "1_1") (pintype "passive"))
      (node (ref "IC12") (pin "1-3") (pinfunction "+IN_1-3") (pintype "input"))
      (node (ref "IC12") (pin "2-3") (pinfunction "+IN_2-3") (pintype "input"))
      (node (ref "R23") (pin "2") (pinfunction "2_2") (pintype "passive"))
      (node (ref "R26") (pin "2") (pinfunction "2_2") (pintype "passive"))
    )
    (net (code "34") (name "Net-(C50-Pad2)") (class "Default")
      (node (ref "C50") (pin "2") (pinfunction "2_2") (pintype "passive"))
      (node (ref "IC18") (pin "1-4") (pinfunction "V-_1-4") (pintype "power_in"))
      (node (ref "IC18") (pin "2-4") (pinfunction "V-_2-4") (pintype "power_in"))
      (node (ref "J5") (pin "2") (pinfunction "2_2") (pintype "passive"))
      (node (ref "J9") (pin "2") (pinfunction "2_2") (pintype "passive"))
    )
    (net (code "35") (name "Net-(C51-Pad2)") (class "Default")
      (node (ref "C51") (pin "2") (pinfunction "2_2") (pintype "passive"))
      (node (ref "R52") (pin "2") (pinfunction "2_2") (pintype "passive"))
    )
    (net (code "36") (name "Net-(CON1-Pad20)") (class "Default")
      (node (ref "CON1") (pin "20") (pinfunction "20_20") (pintype "passive"))
      (node (ref "R7") (pin "1") (pinfunction "1_1") (pintype "passive"))
    )
    (net (code "37") (name "Net-(CON1-Pad21)") (class "Default")
      (node (ref "CON1") (pin "21") (pinfunction "21_21") (pintype "passive"))
      (node (ref "R6") (pin "2") (pinfunction "2_2") (pintype "passive"))
    )
    (net (code "38") (name "Net-(CON1-Pad24)") (class "Default")
      (node (ref "CON1") (pin "24") (pinfunction "24_24") (pintype "passive"))
      (node (ref "R5") (pin "1") (pinfunction "1_1") (pintype "passive"))
    )
    (net (code "39") (name "Net-(CON1-Pad25)") (class "Default")
      (node (ref "CON1") (pin "25") (pinfunction "25_25") (pintype "passive"))
      (node (ref "R4") (pin "2") (pinfunction "2_2") (pintype "passive"))
    )
    (net (code "40") (name "Net-(CON1-Pad28)") (class "Default")
      (node (ref "CON1") (pin "28") (pinfunction "28_28") (pintype "passive"))
      (node (ref "R1") (pin "1") (pinfunction "1_1") (pintype "passive"))
    )
    (net (code "41") (name "Net-(D4-A)") (class "Default")
      (node (ref "D4") (pin "1") (pinfunction "A_1") (pintype "passive"))
      (node (ref "D5") (pin "2") (pinfunction "K_2") (pintype "passive"))
      (node (ref "IC13") (pin "1-5") (pinfunction "+IN_1-5") (pintype "input"))
      (node (ref "IC13") (pin "2-5") (pinfunction "+IN_2-5") (pintype "input"))
      (node (ref "R20") (pin "2") (pinfunction "2_2") (pintype "passive"))
      (node (ref "R41") (pin "2") (pinfunction "2_2") (pintype "passive"))
    )
    (net (code "42") (name "Net-(IC2A-OUT)") (class "Default")
      (node (ref "IC2") (pin "2") (pinfunction "OUT_2") (pintype "output"))
      (node (ref "R2") (pin "2") (pinfunction "2_2") (pintype "passive"))
    )
    (net (code "43") (name "Net-(IC2B-OUT)") (class "Default")
      (node (ref "IC2") (pin "4") (pinfunction "OUT_4") (pintype "output"))
      (node (ref "R24") (pin "2") (pinfunction "2_2") (pintype "passive"))
    )
    (net (code "44") (name "Net-(IC2C-IN)") (class "Default")
      (node (ref "IC2") (pin "5") (pinfunction "IN_5") (pintype "input"))
      (node (ref "R25") (pin "2") (pinfunction "2_2") (pintype "passive"))
    )
    (net (code "45") (name "Net-(IC2D-IN)") (class "Default")
      (node (ref "IC2") (pin "9") (pinfunction "IN_9") (pintype "input"))
      (node (ref "R10") (pin "2") (pinfunction "2_2") (pintype "passive"))
    )
    (net (code "46") (name "Net-(IC2E-IN)") (class "Default")
      (node (ref "IC2") (pin "11") (pinfunction "IN_11") (pintype "input"))
      (node (ref "IC2") (pin "12") (pinfunction "OUT_12") (pintype "output"))
    )
    (net (code "47") (name "Net-(IC4A--IN-Pad1-2)") (class "Default")
      (node (ref "IC4") (pin "1-1") (pinfunction "OUT_1-1") (pintype "output"))
      (node (ref "IC4") (pin "1-2") (pinfunction "-IN_1-2") (pintype "input"))
      (node (ref "IC4") (pin "2-1") (pinfunction "OUT_2-1") (pintype "output"))
      (node (ref "IC4") (pin "2-2") (pinfunction "-IN_2-2") (pintype "input"))
    )
    (net (code "48") (name "Net-(IC5-OUT)") (class "Default")
      (node (ref "IC5") (pin "1") (pinfunction "REF_1") (pintype "input"))
      (node (ref "IC5") (pin "3") (pinfunction "OUT_3") (pintype "bidirectional"))
      (node (ref "R40") (pin "1") (pinfunction "1_1") (pintype "passive"))
      (node (ref "R49") (pin "2") (pinfunction "2_2") (pintype "passive"))
    )
    (net (code "49") (name "Net-(IC6-AIN+)") (class "Default")
      (node (ref "C24") (pin "2") (pinfunction "2_2") (pintype "passive"))
      (node (ref "IC6") (pin "3") (pinfunction "AIN+_3") (pintype "input"))
      (node (ref "R44") (pin "2") (pinfunction "2_2") (pintype "passive"))
    )
    (net (code "50") (name "Net-(IC6-AIN-)") (class "Default")
      (node (ref "C23") (pin "1") (pinfunction "1_1") (pintype "passive"))
      (node (ref "IC6") (pin "4") (pinfunction "AIN-_4") (pintype "bidirectional"))
      (node (ref "R45") (pin "2") (pinfunction "2_2") (pintype "passive"))
    )
    (net (code "51") (name "Net-(IC6-CNVST)") (class "Default")
      (node (ref "IC6") (pin "6") (pinfunction "CNVST_6") (pintype "input"))
      (node (ref "R13") (pin "1") (pinfunction "1_1") (pintype "passive"))
    )
    (net (code "52") (name "Net-(IC6-DVIO)") (class "Default")
      (node (ref "C56") (pin "1") (pinfunction "1_1") (pintype "passive"))
      (node (ref "C6") (pin "1") (pinfunction "1_1") (pintype "passive"))
      (node (ref "FB2") (pin "2") (pinfunction "2_2") (pintype "passive"))
      (node (ref "IC6") (pin "10") (pinfunction "DVIO_10") (pintype "power_in"))
    )
    (net (code "53") (name "Net-(IC6-SCLK)") (class "Default")
      (node (ref "IC6") (pin "8") (pinfunction "SCLK_8") (pintype "input"))
      (node (ref "R24") (pin "1") (pinfunction "1_1") (pintype "passive"))
    )
    (net (code "54") (name "Net-(IC6-SDI)") (class "Default")
      (node (ref "IC6") (pin "9") (pinfunction "SDI_9") (pintype "input"))
      (node (ref "R2") (pin "1") (pinfunction "1_1") (pintype "passive"))
    )
    (net (code "55") (name "Net-(IC6-SDO)") (class "Default")
      (node (ref "IC6") (pin "7") (pinfunction "SDO_7") (pintype "output"))
      (node (ref "R25") (pin "1") (pinfunction "1_1") (pintype "passive"))
    )
    (net (code "56") (name "Net-(IC6-VREF)") (class "Default")
      (node (ref "C12") (pin "1") (pinfunction "1_1") (pintype "passive"))
      (node (ref "C13") (pin "1") (pinfunction "1_1") (pintype "passive"))
      (node (ref "FB3") (pin "2") (pinfunction "2_2") (pintype "passive"))
      (node (ref "IC6") (pin "1") (pinfunction "VREF_1") (pintype "power_in"))
    )
    (net (code "57") (name "Net-(IC10-BYPASS)") (class "Default")
      (node (ref "C36") (pin "1") (pinfunction "1_1") (pintype "passive"))
      (node (ref "IC10") (pin "3") (pinfunction "BYPASS_3") (pintype "passive"))
    )
    (net (code "58") (name "Net-(IC10-VADJ)") (class "Default")
      (node (ref "IC10") (pin "5") (pinfunction "VADJ_5") (pintype "input"))
      (node (ref "R46") (pin "1") (pinfunction "1_1") (pintype "passive"))
      (node (ref "R47") (pin "2") (pinfunction "2_2") (pintype "passive"))
      (node (ref "R51") (pin "1") (pinfunction "1_1") (pintype "passive"))
    )
    (net (code "59") (name "Net-(IC11-BYPASS)") (class "Default")
      (node (ref "C26") (pin "1") (pinfunction "1_1") (pintype "passive"))
      (node (ref "IC11") (pin "4") (pinfunction "BYPASS_4") (pintype "passive"))
    )
    (net (code "60") (name "Net-(IC13B--IN-Pad1-6)") (class "Default")
      (node (ref "IC13") (pin "1-6") (pinfunction "-IN_1-6") (pintype "input"))
      (node (ref "IC13") (pin "2-6") (pinfunction "-IN_2-6") (pintype "input"))
      (node (ref "R15") (pin "1") (pinfunction "1_1") (pintype "passive"))
      (node (ref "R16") (pin "2") (pinfunction "2_2") (pintype "passive"))
      (node (ref "SW1") (pin "3") (pinfunction "3_3") (pintype "passive"))
    )
    (net (code "61") (name "Net-(IC13B-OUT-Pad1-7)") (class "Default")
      (node (ref "IC13") (pin "1-7") (pinfunction "OUT_1-7") (pintype "output"))
      (node (ref "IC13") (pin "2-7") (pinfunction "OUT_2-7") (pintype "output"))
      (node (ref "R15") (pin "2") (pinfunction "2_2") (pintype "passive"))
      (node (ref "R42") (pin "1") (pinfunction "1_1") (pintype "passive"))
      (node (ref "SW1") (pin "1") (pinfunction "1_1") (pintype "passive"))
      (node (ref "SW1") (pin "2") (pinfunction "2_2") (pintype "passive"))
    )
    (net (code "62") (name "Net-(IC14-BYPASS)") (class "Default")
      (node (ref "C32") (pin "1") (pinfunction "1_1") (pintype "passive"))
      (node (ref "IC14") (pin "4") (pinfunction "BYPASS_4") (pintype "passive"))
    )
    (net (code "63") (name "Net-(IC18A--IN-Pad1-2)") (class "Default")
      (node (ref "IC18") (pin "1-1") (pinfunction "OUT_1-1") (pintype "output"))
      (node (ref "IC18") (pin "1-2") (pinfunction "-IN_1-2") (pintype "input"))
      (node (ref "IC18") (pin "2-1") (pinfunction "OUT_2-1") (pintype "output"))
      (node (ref "IC18") (pin "2-2") (pinfunction "-IN_2-2") (pintype "input"))
      (node (ref "J3") (pin "1") (pinfunction "1_1") (pintype "passive"))
      (node (ref "J4") (pin "1") (pinfunction "1_1") (pintype "passive"))
    )
    (net (code "64") (name "Net-(IC18B--IN-Pad1-6)") (class "Default")
      (node (ref "IC18") (pin "1-6") (pinfunction "-IN_1-6") (pintype "input"))
      (node (ref "IC18") (pin "1-7") (pinfunction "OUT_1-7") (pintype "output"))
      (node (ref "IC18") (pin "2-6") (pinfunction "-IN_2-6") (pintype "input"))
      (node (ref "IC18") (pin "2-7") (pinfunction "OUT_2-7") (pintype "output"))
      (node (ref "J1") (pin "1") (pinfunction "1_1") (pintype "passive"))
      (node (ref "J2") (pin "1") (pinfunction "1_1") (pintype "passive"))
    )
    (net (code "65") (name "Net-(IC19A-CK)") (class "Default")
      (node (ref "IC19") (pin "1") (pinfunction "CK_1") (pintype "input"))
      (node (ref "R3") (pin "1") (pinfunction "1_1") (pintype "passive"))
    )
    (net (code "66") (name "Net-(IC19A-~{Q})") (class "Default")
      (node (ref "IC19") (pin "3") (pinfunction "~{Q}_3") (pintype "output"))
      (node (ref "R10") (pin "1") (pinfunction "1_1") (pintype "passive"))
    )
    (net (code "67") (name "Net-(J8-Pad2)") (class "Default")
      (node (ref "J8") (pin "2") (pinfunction "2_2") (pintype "passive"))
      (node (ref "R35") (pin "1") (pinfunction "1_1") (pintype "passive"))
    )
    (net (code "68") (name "Net-(R36-Pad1)") (class "Default")
      (node (ref "R36") (pin "1") (pinfunction "1_1") (pintype "passive"))
      (node (ref "R37") (pin "2") (pinfunction "2_2") (pintype "passive"))
    )
    (net (code "69") (name "V+") (class "Default")
      (node (ref "C39") (pin "1") (pinfunction "1_1") (pintype "passive"))
      (node (ref "C40") (pin "1") (pinfunction "1_1") (pintype "passive"))
      (node (ref "C52") (pin "1") (pinfunction "1_1") (pintype "passive"))
      (node (ref "CON1") (pin "33") (pinfunction "33_33") (pintype "passive"))
      (node (ref "CON1") (pin "34") (pinfunction "34_34") (pintype "passive"))
      (node (ref "IC10") (pin "1") (pinfunction "EN_1") (pintype "input"))
      (node (ref "IC10") (pin "6") (pinfunction "VIN_6") (pintype "power_in"))
      (node (ref "IC11") (pin "1") (pinfunction "VIN_1") (pintype "power_in"))
      (node (ref "IC11") (pin "3") (pinfunction "CONTROL_3") (pintype "input"))
      (node (ref "IC17") (pin "3") (pinfunction "IN_3") (pintype "power_in"))
      (node (ref "TP24") (pin "1") (pinfunction "1_1") (pintype "passive"))
      (node (ref "TP25") (pin "1") (pinfunction "1_1") (pintype "passive"))
    )
    (net (code "70") (name "V-") (class "Default")
      (node (ref "C53") (pin "2") (pinfunction "2_2") (pintype "passive"))
      (node (ref "C59") (pin "2") (pinfunction "2_2") (pintype "passive"))
      (node (ref "CON1") (pin "31") (pinfunction "31_31") (pintype "passive"))
      (node (ref "CON1") (pin "32") (pinfunction "32_32") (pintype "passive"))
      (node (ref "IC16") (pin "2") (pinfunction "IN_2") (pintype "input"))
      (node (ref "IC21") (pin "2") (pinfunction "IN_2") (pintype "input"))
    )
    (net (code "71") (name "VREF") (class "Default")
      (node (ref "C17") (pin "1") (pinfunction "1_1") (pintype "passive"))
      (node (ref "C51") (pin "1") (pinfunction "1_1") (pintype "passive"))
      (node (ref "FB3") (pin "1") (pinfunction "1_1") (pintype "passive"))
      (node (ref "R21") (pin "2") (pinfunction "2_2") (pintype "passive"))
      (node (ref "R22") (pin "2") (pinfunction "2_2") (pintype "passive"))
      (node (ref "R36") (pin "2") (pinfunction "2_2") (pintype "passive"))
    )
    (net (code "72") (name "unconnected-(CON1-Pad1)") (class "Default")
      (node (ref "CON1") (pin "1") (pinfunction "1_1") (pintype "passive"))
    )
    (net (code "73") (name "unconnected-(CON1-Pad4)") (class "Default")
      (node (ref "CON1") (pin "4") (pinfunction "4_4") (pintype "passive"))
    )
    (net (code "74") (name "unconnected-(CON1-Pad5)") (class "Default")
      (node (ref "CON1") (pin "5") (pinfunction "5_5") (pintype "passive"))
    )
    (net (code "75") (name "unconnected-(CON1-Pad8)") (class "Default")
      (node (ref "CON1") (pin "8") (pinfunction "8_8") (pintype "passive"))
    )
    (net (code "76") (name "unconnected-(CON1-Pad9)") (class "Default")
      (node (ref "CON1") (pin "9") (pinfunction "9_9") (pintype "passive"))
    )
    (net (code "77") (name "unconnected-(CON1-Pad12)") (class "Default")
      (node (ref "CON1") (pin "12") (pinfunction "12_12") (pintype "passive"))
    )
    (net (code "78") (name "unconnected-(CON1-Pad13)") (class "Default")
      (node (ref "CON1") (pin "13") (pinfunction "13_13") (pintype "passive"))
    )
    (net (code "79") (name "unconnected-(CON1-Pad16)") (class "Default")
      (node (ref "CON1") (pin "16") (pinfunction "16_16") (pintype "passive"))
    )
    (net (code "80") (name "unconnected-(CON1-Pad17)") (class "Default")
      (node (ref "CON1") (pin "17") (pinfunction "17_17") (pintype "passive"))
    )
    (net (code "81") (name "unconnected-(IC2E-OUT-Pad10)") (class "Default")
      (node (ref "IC2") (pin "10") (pinfunction "OUT_10") (pintype "output"))
    )
  )
)
